# IV-18_clock.net
KiCad netlist of a schematic drawn in EAGLE
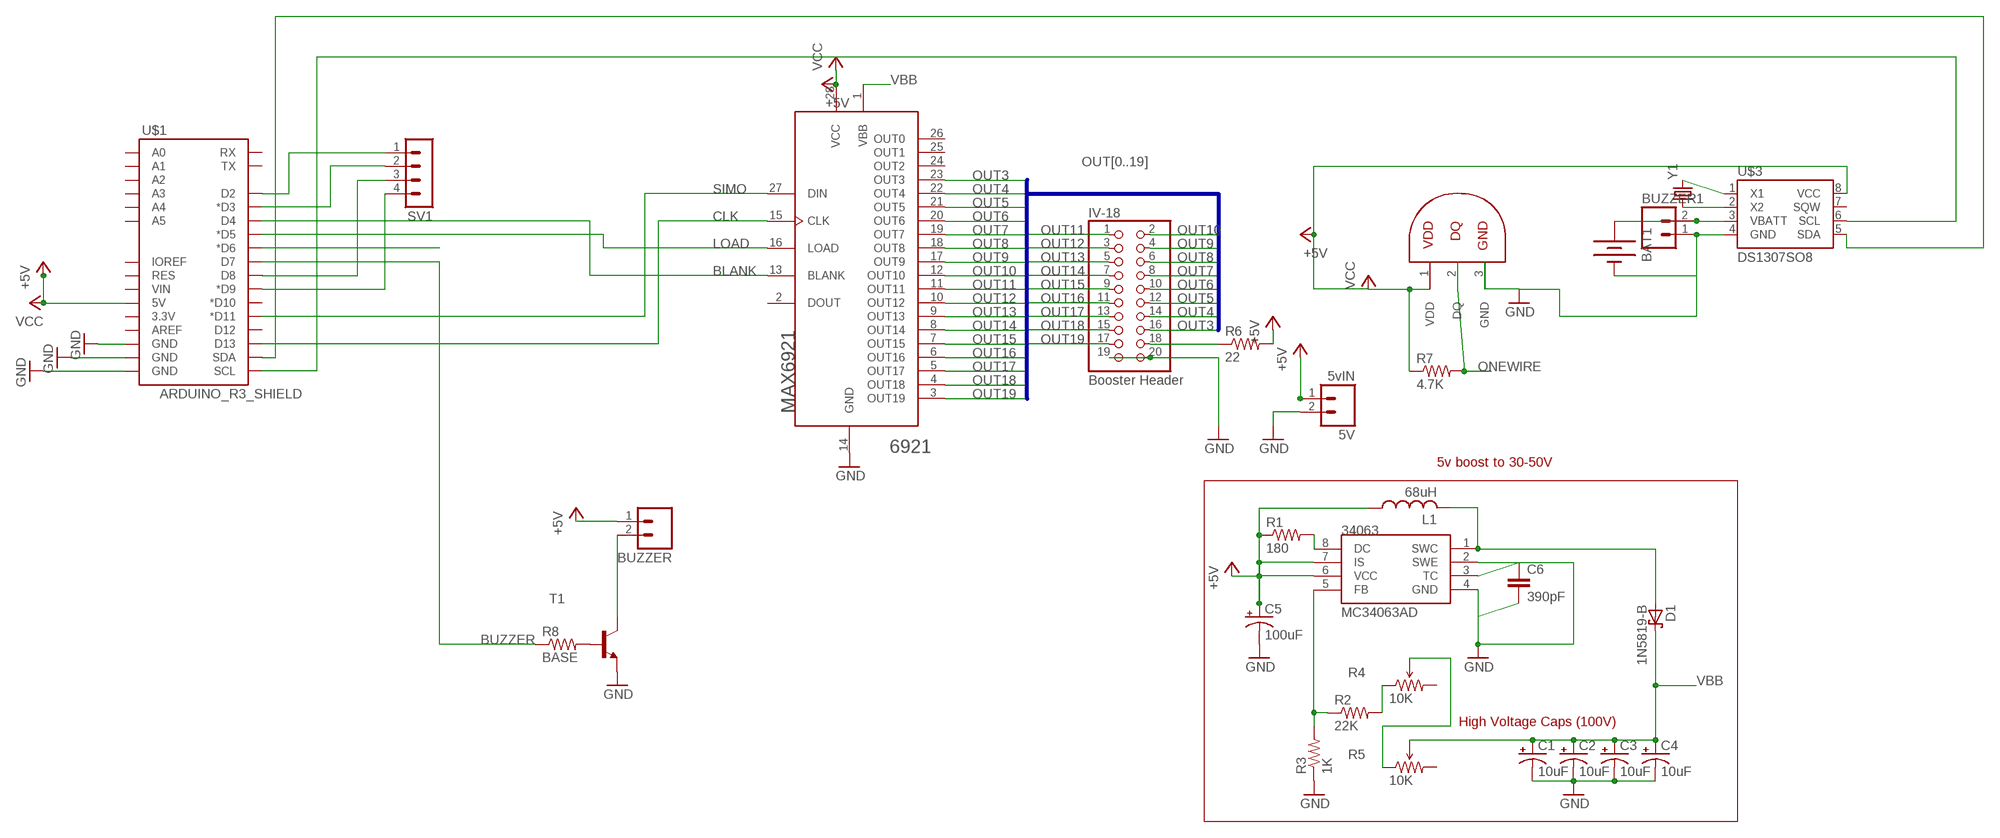
[diagram p0: schematic, sheet 1]

(export (version "E")
  (design (tool "Eeschema 10.0.6"))
  (components
    (comp (ref "5V")
      (value "5vIN")
      (footprint "eagle-import:1X02")
      (libsource (lib "eagle-import") (part "M02PTH"))
    )
    (comp (ref "6921")
      (value "MAX6921_AFSOIC(W)")
      (footprint "eagle-import:SO28L")
      (libsource (lib "eagle-import") (part "MAX6921_AFSOIC(W)"))
    )
    (comp (ref "34063")
      (value "MC34063AD")
      (footprint "eagle-import:SOIC8")
      (libsource (lib "eagle-import") (part "MC34063AD"))
    )
    (comp (ref "BAT1")
      (value "BATTERY20PTH")
      (footprint "eagle-import:BATTCOM_20MM_PTH")
      (libsource (lib "eagle-import") (part "BATTERY20PTH"))
    )
    (comp (ref "BUZZER")
      (value "M02PTH")
      (footprint "eagle-import:1X02")
      (libsource (lib "eagle-import") (part "M02PTH"))
    )
    (comp (ref "BUZZER1")
      (value "M02PTH")
      (footprint "eagle-import:1X02")
      (libsource (lib "eagle-import") (part "M02PTH"))
    )
    (comp (ref "C1")
      (value "10uF")
      (footprint "eagle-import:E2,5-6")
      (libsource (lib "eagle-import") (part "CPOL-USE2.5-6"))
    )
    (comp (ref "C2")
      (value "10uF")
      (footprint "eagle-import:E2,5-6")
      (libsource (lib "eagle-import") (part "CPOL-USE2.5-6"))
    )
    (comp (ref "C3")
      (value "10uF")
      (footprint "eagle-import:E2,5-6")
      (libsource (lib "eagle-import") (part "CPOL-USE2.5-6"))
    )
    (comp (ref "C4")
      (value "10uF")
      (footprint "eagle-import:E2,5-6")
      (libsource (lib "eagle-import") (part "CPOL-USE2.5-6"))
    )
    (comp (ref "C5")
      (value "100uF")
      (footprint "eagle-import:E2,5-6")
      (libsource (lib "eagle-import") (part "CPOL-USE2.5-6"))
    )
    (comp (ref "C6")
      (value "390pF")
      (footprint "eagle-import:CAP-PTH-5MM")
      (libsource (lib "eagle-import") (part "CAPPTH1"))
    )
    (comp (ref "D1")
      (value "1N5819-B")
      (footprint "eagle-import:DO41-7.6")
      (libsource (lib "eagle-import") (part "1N5819-B"))
    )
    (comp (ref "DS18B20")
      (value "DS18B20")
      (footprint "eagle-import:TO92-CBE@1")
      (libsource (lib "eagle-import") (part "DS18B20"))
    )
    (comp (ref "IV-18")
      (value "Booster Header")
      (footprint "eagle-import:2X10")
      (libsource (lib "eagle-import") (part "PINHD-2X10"))
    )
    (comp (ref "L1")
      (value "68uH")
      (footprint "eagle-import:6000-XXXX-RC")
      (libsource (lib "eagle-import") (part "L-US6000-XXX-RC"))
    )
    (comp (ref "R1")
      (value "180")
      (footprint "eagle-import:0204_7")
      (libsource (lib "eagle-import") (part "R-US_0204/7"))
    )
    (comp (ref "R2")
      (value "22K")
      (footprint "eagle-import:0204_7")
      (libsource (lib "eagle-import") (part "R-US_0204/7"))
    )
    (comp (ref "R3")
      (value "1K")
      (footprint "eagle-import:0204_7")
      (libsource (lib "eagle-import") (part "R-US_0204/7"))
    )
    (comp (ref "R4")
      (value "10K")
      (footprint "eagle-import:TRIM_POT_PTH")
      (libsource (lib "eagle-import") (part "TRIMPOTPTH"))
    )
    (comp (ref "R5")
      (value "10K")
      (footprint "eagle-import:TRIM_POT_PTH")
      (libsource (lib "eagle-import") (part "TRIMPOTPTH"))
    )
    (comp (ref "R6")
      (value "22")
      (footprint "eagle-import:0204_7")
      (libsource (lib "eagle-import") (part "R-US_0204/7"))
    )
    (comp (ref "R7")
      (value "4.7K")
      (footprint "eagle-import:0204_7")
      (libsource (lib "eagle-import") (part "R-US_0204/7"))
    )
    (comp (ref "R8")
      (value "BASE")
      (footprint "eagle-import:0204_7")
      (libsource (lib "eagle-import") (part "R-US_0204/7"))
    )
    (comp (ref "SV1")
      (value "MA04-1")
      (footprint "eagle-import:MA04-1")
      (libsource (lib "eagle-import") (part "MA04-1"))
    )
    (comp (ref "T1")
      (value "2N3904-NPN-TO92-EBC")
      (footprint "eagle-import:TO92-EBC")
      (libsource (lib "eagle-import") (part "-NPN-TO92-EBC2N3904"))
    )
    (comp (ref "U$1")
      (value "ARDUINO_R3_SHIELD")
      (footprint "eagle-import:UNO_R3_SHIELD")
      (libsource (lib "eagle-import") (part "ARDUINO_R3_SHIELD"))
    )
    (comp (ref "U$3")
      (value "DS1307SO8")
      (footprint "eagle-import:SO08")
      (libsource (lib "eagle-import") (part "DS1307SO8"))
    )
    (comp (ref "Y1")
      (value "CRYSTALTC26H_EZ")
      (footprint "eagle-import:TC26HEZ")
      (libsource (lib "eagle-import") (part "CRYSTALTC26H_EZ"))
    )
  )
  (nets
    (net (code "4") (name "+5V") (class "Default")
      (node (ref "34063") (pin "6") (pinfunction "VCC_6") (pintype "passive"))
      (node (ref "34063") (pin "7") (pinfunction "IS_7") (pintype "passive"))
      (node (ref "5V") (pin "1") (pinfunction "1_1") (pintype "passive"))
      (node (ref "6921") (pin "28") (pinfunction "VCC_28") (pintype "power_in"))
      (node (ref "BUZZER") (pin "1") (pinfunction "1_1") (pintype "passive"))
      (node (ref "C5") (pin "+") (pinfunction "+_+") (pintype "passive"))
      (node (ref "DS18B20") (pin "1") (pinfunction "VDD_1") (pintype "bidirectional"))
      (node (ref "L1") (pin "1") (pinfunction "1_1") (pintype "passive"))
      (node (ref "R1") (pin "1") (pinfunction "1_1") (pintype "passive"))
      (node (ref "R6") (pin "2") (pinfunction "2_2") (pintype "passive"))
      (node (ref "R7") (pin "1") (pinfunction "1_1") (pintype "passive"))
      (node (ref "U$1") (pin "5V") (pinfunction "5V_5V") (pintype "bidirectional"))
      (node (ref "U$3") (pin "8") (pinfunction "VCC_8") (pintype "bidirectional"))
    )
    (net (code "5") (name "/BLANK") (class "Default")
      (node (ref "6921") (pin "13") (pinfunction "BLANK_13") (pintype "input"))
      (node (ref "U$1") (pin "D4") (pinfunction "D4_D4") (pintype "bidirectional"))
    )
    (net (code "6") (name "/BUZZER") (class "Default")
      (node (ref "R8") (pin "1") (pinfunction "1_1") (pintype "passive"))
      (node (ref "U$1") (pin "D7") (pinfunction "D7_D7") (pintype "bidirectional"))
    )
    (net (code "7") (name "/CLK") (class "Default")
      (node (ref "6921") (pin "15") (pinfunction "CLK_15") (pintype "input"))
      (node (ref "U$1") (pin "D13") (pinfunction "D13_D13") (pintype "bidirectional"))
    )
    (net (code "8") (name "/LOAD") (class "Default")
      (node (ref "6921") (pin "16") (pinfunction "LOAD_16") (pintype "input"))
      (node (ref "U$1") (pin "D5") (pinfunction "*D5_D5") (pintype "bidirectional"))
    )
    (net (code "9") (name "/ONEWIRE") (class "Default")
      (node (ref "DS18B20") (pin "2") (pinfunction "DQ_2") (pintype "bidirectional"))
      (node (ref "R7") (pin "2") (pinfunction "2_2") (pintype "passive"))
      (node (ref "U$1") (pin "D6") (pinfunction "*D6_D6") (pintype "bidirectional"))
    )
    (net (code "10") (name "/OUT3") (class "Default")
      (node (ref "6921") (pin "23") (pinfunction "OUT3_23") (pintype "output"))
      (node (ref "IV-18") (pin "16") (pinfunction "16_16") (pintype "passive"))
    )
    (net (code "11") (name "/OUT4") (class "Default")
      (node (ref "6921") (pin "22") (pinfunction "OUT4_22") (pintype "output"))
      (node (ref "IV-18") (pin "14") (pinfunction "14_14") (pintype "passive"))
    )
    (net (code "12") (name "/OUT5") (class "Default")
      (node (ref "6921") (pin "21") (pinfunction "OUT5_21") (pintype "output"))
      (node (ref "IV-18") (pin "12") (pinfunction "12_12") (pintype "passive"))
    )
    (net (code "13") (name "/OUT6") (class "Default")
      (node (ref "6921") (pin "20") (pinfunction "OUT6_20") (pintype "output"))
      (node (ref "IV-18") (pin "10") (pinfunction "10_10") (pintype "passive"))
    )
    (net (code "14") (name "/OUT7") (class "Default")
      (node (ref "6921") (pin "19") (pinfunction "OUT7_19") (pintype "output"))
      (node (ref "IV-18") (pin "8") (pinfunction "8_8") (pintype "passive"))
    )
    (net (code "15") (name "/OUT8") (class "Default")
      (node (ref "6921") (pin "18") (pinfunction "OUT8_18") (pintype "output"))
      (node (ref "IV-18") (pin "6") (pinfunction "6_6") (pintype "passive"))
    )
    (net (code "16") (name "/OUT9") (class "Default")
      (node (ref "6921") (pin "17") (pinfunction "OUT9_17") (pintype "output"))
      (node (ref "IV-18") (pin "4") (pinfunction "4_4") (pintype "passive"))
    )
    (net (code "17") (name "/OUT10") (class "Default")
      (node (ref "6921") (pin "12") (pinfunction "OUT10_12") (pintype "output"))
      (node (ref "IV-18") (pin "2") (pinfunction "2_2") (pintype "passive"))
    )
    (net (code "18") (name "/OUT11") (class "Default")
      (node (ref "6921") (pin "11") (pinfunction "OUT11_11") (pintype "output"))
      (node (ref "IV-18") (pin "1") (pinfunction "1_1") (pintype "passive"))
    )
    (net (code "19") (name "/OUT12") (class "Default")
      (node (ref "6921") (pin "10") (pinfunction "OUT12_10") (pintype "output"))
      (node (ref "IV-18") (pin "3") (pinfunction "3_3") (pintype "passive"))
    )
    (net (code "20") (name "/OUT13") (class "Default")
      (node (ref "6921") (pin "9") (pinfunction "OUT13_9") (pintype "output"))
      (node (ref "IV-18") (pin "5") (pinfunction "5_5") (pintype "passive"))
    )
    (net (code "21") (name "/OUT14") (class "Default")
      (node (ref "6921") (pin "8") (pinfunction "OUT14_8") (pintype "output"))
      (node (ref "IV-18") (pin "7") (pinfunction "7_7") (pintype "passive"))
    )
    (net (code "22") (name "/OUT15") (class "Default")
      (node (ref "6921") (pin "7") (pinfunction "OUT15_7") (pintype "output"))
      (node (ref "IV-18") (pin "9") (pinfunction "9_9") (pintype "passive"))
    )
    (net (code "23") (name "/OUT16") (class "Default")
      (node (ref "6921") (pin "6") (pinfunction "OUT16_6") (pintype "output"))
      (node (ref "IV-18") (pin "11") (pinfunction "11_11") (pintype "passive"))
    )
    (net (code "24") (name "/OUT17") (class "Default")
      (node (ref "6921") (pin "5") (pinfunction "OUT17_5") (pintype "output"))
      (node (ref "IV-18") (pin "13") (pinfunction "13_13") (pintype "passive"))
    )
    (net (code "25") (name "/OUT18") (class "Default")
      (node (ref "6921") (pin "4") (pinfunction "OUT18_4") (pintype "output"))
      (node (ref "IV-18") (pin "15") (pinfunction "15_15") (pintype "passive"))
    )
    (net (code "26") (name "/OUT19") (class "Default")
      (node (ref "6921") (pin "3") (pinfunction "OUT19_3") (pintype "output"))
      (node (ref "IV-18") (pin "17") (pinfunction "17_17") (pintype "passive"))
    )
    (net (code "28") (name "/SIMO") (class "Default")
      (node (ref "6921") (pin "27") (pinfunction "DIN_27") (pintype "input"))
      (node (ref "U$1") (pin "D11") (pinfunction "*D11_D11") (pintype "bidirectional"))
    )
    (net (code "29") (name "/VBB") (class "Default")
      (node (ref "6921") (pin "1") (pinfunction "VBB_1") (pintype "power_in"))
      (node (ref "C1") (pin "+") (pinfunction "+_+") (pintype "passive"))
      (node (ref "C2") (pin "+") (pinfunction "+_+") (pintype "passive"))
      (node (ref "C3") (pin "+") (pinfunction "+_+") (pintype "passive"))
      (node (ref "C4") (pin "+") (pinfunction "+_+") (pintype "passive"))
      (node (ref "D1") (pin "C") (pinfunction "C_C") (pintype "passive"))
      (node (ref "R5") (pin "2") (pinfunction "WIPER_2") (pintype "passive"))
    )
    (net (code "30") (name "GND") (class "Default")
      (node (ref "34063") (pin "2") (pinfunction "SWE_2") (pintype "passive"))
      (node (ref "34063") (pin "4") (pinfunction "GND_4") (pintype "passive"))
      (node (ref "5V") (pin "2") (pinfunction "2_2") (pintype "passive"))
      (node (ref "6921") (pin "14") (pinfunction "GND_14") (pintype "power_in"))
      (node (ref "BAT1") (pin "2") (pinfunction "-_2") (pintype "power_in"))
      (node (ref "BUZZER1") (pin "1") (pinfunction "1_1") (pintype "passive"))
      (node (ref "C1") (pin "-") (pinfunction "-_-") (pintype "passive"))
      (node (ref "C2") (pin "-") (pinfunction "-_-") (pintype "passive"))
      (node (ref "C3") (pin "-") (pinfunction "-_-") (pintype "passive"))
      (node (ref "C4") (pin "-") (pinfunction "-_-") (pintype "passive"))
      (node (ref "C5") (pin "-") (pinfunction "-_-") (pintype "passive"))
      (node (ref "C6") (pin "2") (pinfunction "2_2") (pintype "passive"))
      (node (ref "DS18B20") (pin "3") (pinfunction "GND_3") (pintype "bidirectional"))
      (node (ref "IV-18") (pin "19") (pinfunction "19_19") (pintype "passive"))
      (node (ref "IV-18") (pin "20") (pinfunction "20_20") (pintype "passive"))
      (node (ref "R3") (pin "1") (pinfunction "1_1") (pintype "passive"))
      (node (ref "T1") (pin "E") (pinfunction "E_E") (pintype "passive"))
      (node (ref "U$1") (pin "GND@0") (pinfunction "GND_GND@0") (pintype "bidirectional"))
      (node (ref "U$1") (pin "GND@1") (pinfunction "GND_GND@1") (pintype "bidirectional"))
      (node (ref "U$1") (pin "GND@2") (pinfunction "GND_GND@2") (pintype "bidirectional"))
      (node (ref "U$3") (pin "4") (pinfunction "GND_4") (pintype "bidirectional"))
    )
    (net (code "31") (name "Net-(34063-DC)") (class "Default")
      (node (ref "34063") (pin "8") (pinfunction "DC_8") (pintype "passive"))
      (node (ref "R1") (pin "2") (pinfunction "2_2") (pintype "passive"))
    )
    (net (code "32") (name "Net-(34063-FB)") (class "Default")
      (node (ref "34063") (pin "5") (pinfunction "FB_5") (pintype "passive"))
      (node (ref "R2") (pin "1") (pinfunction "1_1") (pintype "passive"))
      (node (ref "R3") (pin "2") (pinfunction "2_2") (pintype "passive"))
    )
    (net (code "33") (name "Net-(34063-SWC)") (class "Default")
      (node (ref "34063") (pin "1") (pinfunction "SWC_1") (pintype "passive"))
      (node (ref "D1") (pin "A") (pinfunction "A_A") (pintype "passive"))
      (node (ref "L1") (pin "2") (pinfunction "2_2") (pintype "passive"))
    )
    (net (code "34") (name "Net-(34063-TC)") (class "Default")
      (node (ref "34063") (pin "3") (pinfunction "TC_3") (pintype "passive"))
      (node (ref "C6") (pin "1") (pinfunction "1_1") (pintype "passive"))
    )
    (net (code "35") (name "Net-(BAT1-+)") (class "Default")
      (node (ref "BAT1") (pin "1") (pinfunction "+_1") (pintype "power_in"))
      (node (ref "BUZZER1") (pin "2") (pinfunction "2_2") (pintype "passive"))
      (node (ref "U$3") (pin "3") (pinfunction "VBATT_3") (pintype "bidirectional"))
    )
    (net (code "36") (name "Net-(BUZZER-Pad2)") (class "Default")
      (node (ref "BUZZER") (pin "2") (pinfunction "2_2") (pintype "passive"))
      (node (ref "T1") (pin "C") (pinfunction "C_C") (pintype "passive"))
    )
    (net (code "37") (name "Net-(IV-18-Pad18)") (class "Default")
      (node (ref "IV-18") (pin "18") (pinfunction "18_18") (pintype "passive"))
      (node (ref "R6") (pin "1") (pinfunction "1_1") (pintype "passive"))
    )
    (net (code "38") (name "Net-(R4-CCW)") (class "Default")
      (node (ref "R2") (pin "2") (pinfunction "2_2") (pintype "passive"))
      (node (ref "R4") (pin "1") (pinfunction "CCW_1") (pintype "passive"))
    )
    (net (code "39") (name "Net-(R4-WIPER)") (class "Default")
      (node (ref "R4") (pin "2") (pinfunction "WIPER_2") (pintype "passive"))
      (node (ref "R5") (pin "1") (pinfunction "CCW_1") (pintype "passive"))
    )
    (net (code "40") (name "Net-(R8-Pad2)") (class "Default")
      (node (ref "R8") (pin "2") (pinfunction "2_2") (pintype "passive"))
      (node (ref "T1") (pin "B") (pinfunction "B_B") (pintype "passive"))
    )
    (net (code "41") (name "Net-(SV1-Pad1)") (class "Default")
      (node (ref "SV1") (pin "1") (pinfunction "1_1") (pintype "passive"))
      (node (ref "U$1") (pin "D2") (pinfunction "D2_D2") (pintype "bidirectional"))
    )
    (net (code "42") (name "Net-(SV1-Pad3)") (class "Default")
      (node (ref "SV1") (pin "3") (pinfunction "3_3") (pintype "passive"))
      (node (ref "U$1") (pin "D8") (pinfunction "D8_D8") (pintype "bidirectional"))
    )
    (net (code "43") (name "Net-(U$1-*D3)") (class "Default")
      (node (ref "SV1") (pin "2") (pinfunction "2_2") (pintype "passive"))
      (node (ref "U$1") (pin "D3") (pinfunction "*D3_D3") (pintype "bidirectional"))
    )
    (net (code "44") (name "Net-(U$1-*D9)") (class "Default")
      (node (ref "SV1") (pin "4") (pinfunction "4_4") (pintype "passive"))
      (node (ref "U$1") (pin "D9") (pinfunction "*D9_D9") (pintype "bidirectional"))
    )
    (net (code "45") (name "Net-(U$3-SCL)") (class "Default")
      (node (ref "U$1") (pin "SCL") (pinfunction "SCL_SCL") (pintype "bidirectional"))
      (node (ref "U$3") (pin "6") (pinfunction "SCL_6") (pintype "bidirectional"))
    )
    (net (code "46") (name "Net-(U$3-SDA)") (class "Default")
      (node (ref "U$1") (pin "SDA") (pinfunction "SDA_SDA") (pintype "bidirectional"))
      (node (ref "U$3") (pin "5") (pinfunction "SDA_5") (pintype "bidirectional"))
    )
    (net (code "47") (name "Net-(U$3-X1)") (class "Default")
      (node (ref "U$3") (pin "1") (pinfunction "X1_1") (pintype "bidirectional"))
      (node (ref "Y1") (pin "2") (pinfunction "2_2") (pintype "passive"))
    )
    (net (code "48") (name "Net-(U$3-X2)") (class "Default")
      (node (ref "U$3") (pin "2") (pinfunction "X2_2") (pintype "bidirectional"))
      (node (ref "Y1") (pin "1") (pinfunction "1_1") (pintype "passive"))
    )
    (net (code "49") (name "unconnected-(6921-DOUT-Pad2)") (class "Default")
      (node (ref "6921") (pin "2") (pinfunction "DOUT_2") (pintype "output"))
    )
    (net (code "50") (name "unconnected-(6921-OUT0-Pad26)") (class "Default")
      (node (ref "6921") (pin "26") (pinfunction "OUT0_26") (pintype "output"))
    )
    (net (code "51") (name "unconnected-(6921-OUT1-Pad25)") (class "Default")
      (node (ref "6921") (pin "25") (pinfunction "OUT1_25") (pintype "output"))
    )
    (net (code "52") (name "unconnected-(6921-OUT2-Pad24)") (class "Default")
      (node (ref "6921") (pin "24") (pinfunction "OUT2_24") (pintype "output"))
    )
    (net (code "53") (name "unconnected-(R4-CW-Pad3)") (class "Default")
      (node (ref "R4") (pin "3") (pinfunction "CW_3") (pintype "passive"))
    )
    (net (code "54") (name "unconnected-(R5-CW-Pad3)") (class "Default")
      (node (ref "R5") (pin "3") (pinfunction "CW_3") (pintype "passive"))
    )
    (net (code "55") (name "unconnected-(U$1-*D10-PadD10)") (class "Default")
      (node (ref "U$1") (pin "D10") (pinfunction "*D10_D10") (pintype "bidirectional"))
    )
    (net (code "56") (name "unconnected-(U$1-Pad3.3V)") (class "Default")
      (node (ref "U$1") (pin "3.3V") (pinfunction "3.3V_3.3V") (pintype "bidirectional"))
    )
    (net (code "57") (name "unconnected-(U$1-PadA0)") (class "Default")
      (node (ref "U$1") (pin "A0") (pinfunction "A0_A0") (pintype "bidirectional"))
    )
    (net (code "58") (name "unconnected-(U$1-PadA1)") (class "Default")
      (node (ref "U$1") (pin "A1") (pinfunction "A1_A1") (pintype "bidirectional"))
    )
    (net (code "59") (name "unconnected-(U$1-PadA2)") (class "Default")
      (node (ref "U$1") (pin "A2") (pinfunction "A2_A2") (pintype "bidirectional"))
    )
    (net (code "60") (name "unconnected-(U$1-PadA3)") (class "Default")
      (node (ref "U$1") (pin "A3") (pinfunction "A3_A3") (pintype "bidirectional"))
    )
    (net (code "61") (name "unconnected-(U$1-PadA4)") (class "Default")
      (node (ref "U$1") (pin "A4") (pinfunction "A4_A4") (pintype "bidirectional"))
    )
    (net (code "62") (name "unconnected-(U$1-PadA5)") (class "Default")
      (node (ref "U$1") (pin "A5") (pinfunction "A5_A5") (pintype "bidirectional"))
    )
    (net (code "63") (name "unconnected-(U$1-PadAREF)") (class "Default")
      (node (ref "U$1") (pin "AREF") (pinfunction "AREF_AREF") (pintype "bidirectional"))
    )
    (net (code "64") (name "unconnected-(U$1-PadD12)") (class "Default")
      (node (ref "U$1") (pin "D12") (pinfunction "D12_D12") (pintype "bidirectional"))
    )
    (net (code "65") (name "unconnected-(U$1-PadIOREF)") (class "Default")
      (node (ref "U$1") (pin "IOREF") (pinfunction "IOREF_IOREF") (pintype "bidirectional"))
    )
    (net (code "66") (name "unconnected-(U$1-PadRES)") (class "Default")
      (node (ref "U$1") (pin "RES") (pinfunction "RES_RES") (pintype "bidirectional"))
    )
    (net (code "67") (name "unconnected-(U$1-PadRX)") (class "Default")
      (node (ref "U$1") (pin "RX") (pinfunction "RX_RX") (pintype "bidirectional"))
    )
    (net (code "68") (name "unconnected-(U$1-PadTX)") (class "Default")
      (node (ref "U$1") (pin "TX") (pinfunction "TX_TX") (pintype "bidirectional"))
    )
    (net (code "69") (name "unconnected-(U$1-PadVIN)") (class "Default")
      (node (ref "U$1") (pin "VIN") (pinfunction "VIN_VIN") (pintype "bidirectional"))
    )
    (net (code "70") (name "unconnected-(U$3-SQW-Pad7)") (class "Default")
      (node (ref "U$3") (pin "7") (pinfunction "SQW_7") (pintype "bidirectional"))
    )
  )
)
